# probe.net
KiCad netlist of a schematic drawn in EAGLE
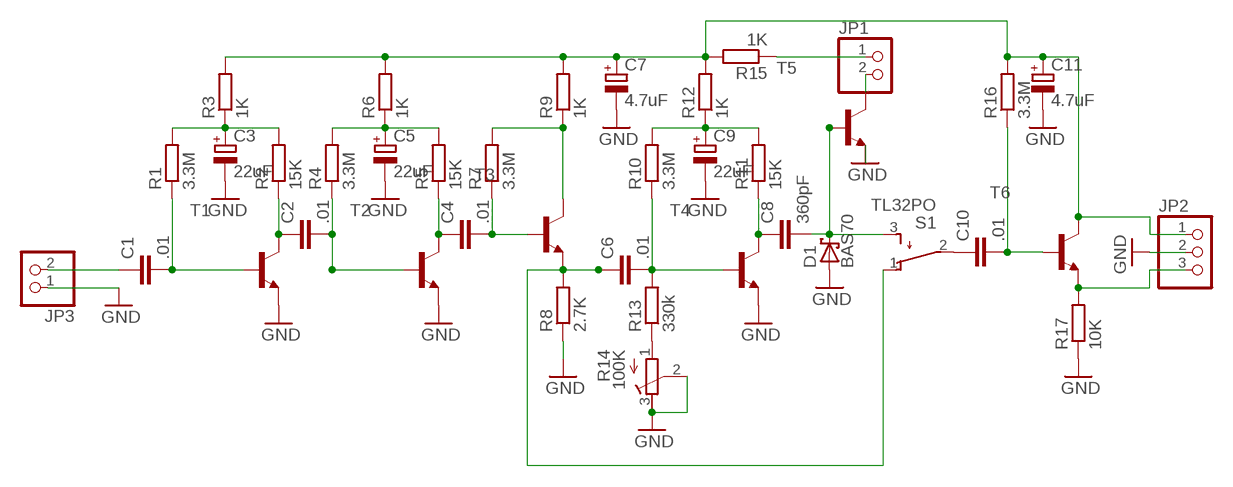
[diagram p0: schematic, sheet 1]

(export (version "E")
  (design (tool "Eeschema 10.0.6"))
  (components
    (comp (ref "C1")
      (value ".01")
      (footprint "eagle-import:C0603")
      (libsource (lib "eagle-import") (part "C-EUC0603"))
    )
    (comp (ref "C2")
      (value ".01")
      (footprint "eagle-import:C0603")
      (libsource (lib "eagle-import") (part "C-EUC0603"))
    )
    (comp (ref "C3")
      (value "22uF")
      (footprint "eagle-import:CT3528")
      (libsource (lib "eagle-import") (part "CPOL-EUCT3528"))
    )
    (comp (ref "C4")
      (value ".01")
      (footprint "eagle-import:C0603")
      (libsource (lib "eagle-import") (part "C-EUC0603"))
    )
    (comp (ref "C5")
      (value "22uF")
      (footprint "eagle-import:CT3528")
      (libsource (lib "eagle-import") (part "CPOL-EUCT3528"))
    )
    (comp (ref "C6")
      (value ".01")
      (footprint "eagle-import:C0603")
      (libsource (lib "eagle-import") (part "C-EUC0603"))
    )
    (comp (ref "C7")
      (value "4.7uF")
      (footprint "eagle-import:CT3528")
      (libsource (lib "eagle-import") (part "CPOL-EUCT3528"))
    )
    (comp (ref "C8")
      (value "360pF")
      (footprint "eagle-import:C0603")
      (libsource (lib "eagle-import") (part "C-EUC0603"))
    )
    (comp (ref "C9")
      (value "22uF")
      (footprint "eagle-import:CT3528")
      (libsource (lib "eagle-import") (part "CPOL-EUCT3528"))
    )
    (comp (ref "C10")
      (value ".01")
      (footprint "eagle-import:C0603")
      (libsource (lib "eagle-import") (part "C-EUC0603"))
    )
    (comp (ref "C11")
      (value "4.7uF")
      (footprint "eagle-import:CT3528")
      (libsource (lib "eagle-import") (part "CPOL-EUCT3528"))
    )
    (comp (ref "D1")
      (value "BAS70")
      (footprint "eagle-import:SOT23")
      (libsource (lib "eagle-import") (part "BAS70"))
    )
    (comp (ref "JP1")
      (value "PINHD-1X2")
      (footprint "eagle-import:1X02")
      (libsource (lib "eagle-import") (part "PINHD-1X2"))
    )
    (comp (ref "JP2")
      (value "PINHD-1X3")
      (footprint "eagle-import:1X03")
      (libsource (lib "eagle-import") (part "PINHD-1X3"))
    )
    (comp (ref "JP3")
      (value "PINHD-1X2")
      (footprint "eagle-import:1X02")
      (libsource (lib "eagle-import") (part "PINHD-1X2"))
    )
    (comp (ref "R1")
      (value "3.3M")
      (footprint "eagle-import:R0603")
      (libsource (lib "eagle-import") (part "R-EU_R0603"))
    )
    (comp (ref "R2")
      (value "15K")
      (footprint "eagle-import:R0603")
      (libsource (lib "eagle-import") (part "R-EU_R0603"))
    )
    (comp (ref "R3")
      (value "1K")
      (footprint "eagle-import:R0603")
      (libsource (lib "eagle-import") (part "R-EU_R0603"))
    )
    (comp (ref "R4")
      (value "3.3M")
      (footprint "eagle-import:R0603")
      (libsource (lib "eagle-import") (part "R-EU_R0603"))
    )
    (comp (ref "R5")
      (value "15K")
      (footprint "eagle-import:R0603")
      (libsource (lib "eagle-import") (part "R-EU_R0603"))
    )
    (comp (ref "R6")
      (value "1K")
      (footprint "eagle-import:R0603")
      (libsource (lib "eagle-import") (part "R-EU_R0603"))
    )
    (comp (ref "R7")
      (value "3.3M")
      (footprint "eagle-import:R0603")
      (libsource (lib "eagle-import") (part "R-EU_R0603"))
    )
    (comp (ref "R8")
      (value "2.7K")
      (footprint "eagle-import:R0603")
      (libsource (lib "eagle-import") (part "R-EU_R0603"))
    )
    (comp (ref "R9")
      (value "1K")
      (footprint "eagle-import:R0603")
      (libsource (lib "eagle-import") (part "R-EU_R0603"))
    )
    (comp (ref "R10")
      (value "3.3M")
      (footprint "eagle-import:R0603")
      (libsource (lib "eagle-import") (part "R-EU_R0603"))
    )
    (comp (ref "R11")
      (value "15K")
      (footprint "eagle-import:R0603")
      (libsource (lib "eagle-import") (part "R-EU_R0603"))
    )
    (comp (ref "R12")
      (value "1K")
      (footprint "eagle-import:R0603")
      (libsource (lib "eagle-import") (part "R-EU_R0603"))
    )
    (comp (ref "R13")
      (value "330k")
      (footprint "eagle-import:R0603")
      (libsource (lib "eagle-import") (part "R-EU_R0603"))
    )
    (comp (ref "R14")
      (value "100K")
      (footprint "eagle-import:RTRIM3103")
      (libsource (lib "eagle-import") (part "R-TRIMM3103"))
    )
    (comp (ref "R15")
      (value "1K")
      (footprint "eagle-import:R0603")
      (libsource (lib "eagle-import") (part "R-EU_R0603"))
    )
    (comp (ref "R16")
      (value "3.3M")
      (footprint "eagle-import:R0603")
      (libsource (lib "eagle-import") (part "R-EU_R0603"))
    )
    (comp (ref "R17")
      (value "10K")
      (footprint "eagle-import:R0603")
      (libsource (lib "eagle-import") (part "R-EU_R0603"))
    )
    (comp (ref "S1")
      (value "TL32PO")
      (footprint "eagle-import:TL3XPO")
      (libsource (lib "eagle-import") (part "TL32PO"))
    )
    (comp (ref "T1")
      (value "BC848-NPN-SOT23-BEC")
      (footprint "eagle-import:SOT23-BEC")
      (libsource (lib "eagle-import") (part "-NPN-SOT23-BECBC848"))
    )
    (comp (ref "T2")
      (value "BC848-NPN-SOT23-BEC")
      (footprint "eagle-import:SOT23-BEC")
      (libsource (lib "eagle-import") (part "-NPN-SOT23-BECBC848"))
    )
    (comp (ref "T3")
      (value "BC848-NPN-SOT23-BEC")
      (footprint "eagle-import:SOT23-BEC")
      (libsource (lib "eagle-import") (part "-NPN-SOT23-BECBC848"))
    )
    (comp (ref "T4")
      (value "BC848-NPN-SOT23-BEC")
      (footprint "eagle-import:SOT23-BEC")
      (libsource (lib "eagle-import") (part "-NPN-SOT23-BECBC848"))
    )
    (comp (ref "T5")
      (value "BC848-NPN-SOT23-BEC")
      (footprint "eagle-import:SOT23-BEC")
      (libsource (lib "eagle-import") (part "-NPN-SOT23-BECBC848"))
    )
    (comp (ref "T6")
      (value "BC848-NPN-SOT23-BEC")
      (footprint "eagle-import:SOT23-BEC")
      (libsource (lib "eagle-import") (part "-NPN-SOT23-BECBC848"))
    )
  )
  (nets
    (net (code "1") (name "GND") (class "Default")
      (node (ref "C11") (pin "-") (pinfunction "-_-") (pintype "passive"))
      (node (ref "C3") (pin "-") (pinfunction "-_-") (pintype "passive"))
      (node (ref "C5") (pin "-") (pinfunction "-_-") (pintype "passive"))
      (node (ref "C7") (pin "-") (pinfunction "-_-") (pintype "passive"))
      (node (ref "C9") (pin "-") (pinfunction "-_-") (pintype "passive"))
      (node (ref "D1") (pin "1") (pinfunction "A_1") (pintype "passive"))
      (node (ref "JP2") (pin "2") (pinfunction "2_2") (pintype "passive"))
      (node (ref "JP3") (pin "1") (pinfunction "1_1") (pintype "passive"))
      (node (ref "R14") (pin "2") (pinfunction "S_2") (pintype "passive"))
      (node (ref "R14") (pin "3") (pinfunction "E_3") (pintype "passive"))
      (node (ref "R17") (pin "1") (pinfunction "1_1") (pintype "passive"))
      (node (ref "R8") (pin "1") (pinfunction "1_1") (pintype "passive"))
      (node (ref "T1") (pin "E") (pinfunction "E_E") (pintype "passive"))
      (node (ref "T2") (pin "E") (pinfunction "E_E") (pintype "passive"))
      (node (ref "T4") (pin "E") (pinfunction "E_E") (pintype "passive"))
      (node (ref "T5") (pin "E") (pinfunction "E_E") (pintype "passive"))
    )
    (net (code "2") (name "Net-(C1-Pad1)") (class "Default")
      (node (ref "C1") (pin "1") (pinfunction "1_1") (pintype "passive"))
      (node (ref "JP3") (pin "2") (pinfunction "2_2") (pintype "passive"))
    )
    (net (code "3") (name "Net-(C1-Pad2)") (class "Default")
      (node (ref "C1") (pin "2") (pinfunction "2_2") (pintype "passive"))
      (node (ref "R1") (pin "1") (pinfunction "1_1") (pintype "passive"))
      (node (ref "T1") (pin "B") (pinfunction "B_B") (pintype "passive"))
    )
    (net (code "4") (name "Net-(C2-Pad1)") (class "Default")
      (node (ref "C2") (pin "1") (pinfunction "1_1") (pintype "passive"))
      (node (ref "R2") (pin "1") (pinfunction "1_1") (pintype "passive"))
      (node (ref "T1") (pin "C") (pinfunction "C_C") (pintype "passive"))
    )
    (net (code "5") (name "Net-(C2-Pad2)") (class "Default")
      (node (ref "C2") (pin "2") (pinfunction "2_2") (pintype "passive"))
      (node (ref "R4") (pin "1") (pinfunction "1_1") (pintype "passive"))
      (node (ref "T2") (pin "B") (pinfunction "B_B") (pintype "passive"))
    )
    (net (code "6") (name "Net-(C3-Pad+)") (class "Default")
      (node (ref "C3") (pin "+") (pinfunction "+_+") (pintype "passive"))
      (node (ref "R1") (pin "2") (pinfunction "2_2") (pintype "passive"))
      (node (ref "R2") (pin "2") (pinfunction "2_2") (pintype "passive"))
      (node (ref "R3") (pin "1") (pinfunction "1_1") (pintype "passive"))
    )
    (net (code "7") (name "Net-(C4-Pad1)") (class "Default")
      (node (ref "C4") (pin "1") (pinfunction "1_1") (pintype "passive"))
      (node (ref "R5") (pin "1") (pinfunction "1_1") (pintype "passive"))
      (node (ref "T2") (pin "C") (pinfunction "C_C") (pintype "passive"))
    )
    (net (code "8") (name "Net-(C4-Pad2)") (class "Default")
      (node (ref "C4") (pin "2") (pinfunction "2_2") (pintype "passive"))
      (node (ref "R7") (pin "1") (pinfunction "1_1") (pintype "passive"))
      (node (ref "T3") (pin "B") (pinfunction "B_B") (pintype "passive"))
    )
    (net (code "9") (name "Net-(C5-Pad+)") (class "Default")
      (node (ref "C5") (pin "+") (pinfunction "+_+") (pintype "passive"))
      (node (ref "R4") (pin "2") (pinfunction "2_2") (pintype "passive"))
      (node (ref "R5") (pin "2") (pinfunction "2_2") (pintype "passive"))
      (node (ref "R6") (pin "1") (pinfunction "1_1") (pintype "passive"))
    )
    (net (code "10") (name "Net-(C6-Pad2)") (class "Default")
      (node (ref "C6") (pin "2") (pinfunction "2_2") (pintype "passive"))
      (node (ref "R10") (pin "1") (pinfunction "1_1") (pintype "passive"))
      (node (ref "R13") (pin "2") (pinfunction "2_2") (pintype "passive"))
      (node (ref "T4") (pin "B") (pinfunction "B_B") (pintype "passive"))
    )
    (net (code "11") (name "Net-(C8-Pad1)") (class "Default")
      (node (ref "C8") (pin "1") (pinfunction "1_1") (pintype "passive"))
      (node (ref "R11") (pin "1") (pinfunction "1_1") (pintype "passive"))
      (node (ref "T4") (pin "C") (pinfunction "C_C") (pintype "passive"))
    )
    (net (code "12") (name "Net-(C9-Pad+)") (class "Default")
      (node (ref "C9") (pin "+") (pinfunction "+_+") (pintype "passive"))
      (node (ref "R10") (pin "2") (pinfunction "2_2") (pintype "passive"))
      (node (ref "R11") (pin "2") (pinfunction "2_2") (pintype "passive"))
      (node (ref "R12") (pin "1") (pinfunction "1_1") (pintype "passive"))
    )
    (net (code "13") (name "Net-(C10-Pad2)") (class "Default")
      (node (ref "C10") (pin "2") (pinfunction "2_2") (pintype "passive"))
      (node (ref "R16") (pin "1") (pinfunction "1_1") (pintype "passive"))
      (node (ref "T6") (pin "B") (pinfunction "B_B") (pintype "passive"))
    )
    (net (code "14") (name "Net-(C11-Pad+)") (class "Default")
      (node (ref "C11") (pin "+") (pinfunction "+_+") (pintype "passive"))
      (node (ref "C7") (pin "+") (pinfunction "+_+") (pintype "passive"))
      (node (ref "JP2") (pin "1") (pinfunction "1_1") (pintype "passive"))
      (node (ref "R12") (pin "2") (pinfunction "2_2") (pintype "passive"))
      (node (ref "R15") (pin "2") (pinfunction "2_2") (pintype "passive"))
      (node (ref "R16") (pin "2") (pinfunction "2_2") (pintype "passive"))
      (node (ref "R3") (pin "2") (pinfunction "2_2") (pintype "passive"))
      (node (ref "R6") (pin "2") (pinfunction "2_2") (pintype "passive"))
      (node (ref "R9") (pin "2") (pinfunction "2_2") (pintype "passive"))
      (node (ref "T6") (pin "C") (pinfunction "C_C") (pintype "passive"))
    )
    (net (code "15") (name "Net-(D1-C)") (class "Default")
      (node (ref "C8") (pin "2") (pinfunction "2_2") (pintype "passive"))
      (node (ref "D1") (pin "3") (pinfunction "C_3") (pintype "passive"))
      (node (ref "S1") (pin "3") (pinfunction "S_3") (pintype "passive"))
      (node (ref "T5") (pin "B") (pinfunction "B_B") (pintype "passive"))
    )
    (net (code "16") (name "Net-(JP1-Pad1)") (class "Default")
      (node (ref "JP1") (pin "1") (pinfunction "1_1") (pintype "passive"))
      (node (ref "R15") (pin "1") (pinfunction "1_1") (pintype "passive"))
    )
    (net (code "17") (name "Net-(JP1-Pad2)") (class "Default")
      (node (ref "JP1") (pin "2") (pinfunction "2_2") (pintype "passive"))
      (node (ref "T5") (pin "C") (pinfunction "C_C") (pintype "passive"))
    )
    (net (code "18") (name "Net-(JP2-Pad3)") (class "Default")
      (node (ref "JP2") (pin "3") (pinfunction "3_3") (pintype "passive"))
      (node (ref "R17") (pin "2") (pinfunction "2_2") (pintype "passive"))
      (node (ref "T6") (pin "E") (pinfunction "E_E") (pintype "passive"))
    )
    (net (code "19") (name "Net-(R7-Pad2)") (class "Default")
      (node (ref "R7") (pin "2") (pinfunction "2_2") (pintype "passive"))
      (node (ref "R9") (pin "1") (pinfunction "1_1") (pintype "passive"))
      (node (ref "T3") (pin "C") (pinfunction "C_C") (pintype "passive"))
    )
    (net (code "20") (name "Net-(R14-A)") (class "Default")
      (node (ref "R13") (pin "1") (pinfunction "1_1") (pintype "passive"))
      (node (ref "R14") (pin "1") (pinfunction "A_1") (pintype "passive"))
    )
    (net (code "21") (name "Net-(S1-O)") (class "Default")
      (node (ref "C6") (pin "1") (pinfunction "1_1") (pintype "passive"))
      (node (ref "R8") (pin "2") (pinfunction "2_2") (pintype "passive"))
      (node (ref "S1") (pin "1") (pinfunction "O_1") (pintype "passive"))
      (node (ref "T3") (pin "E") (pinfunction "E_E") (pintype "passive"))
    )
    (net (code "22") (name "Net-(S1-P)") (class "Default")
      (node (ref "C10") (pin "1") (pinfunction "1_1") (pintype "passive"))
      (node (ref "S1") (pin "2") (pinfunction "P_2") (pintype "passive"))
    )
  )
)
